# Positive_Ioniser.net
KiCad netlist of a schematic drawn in EAGLE
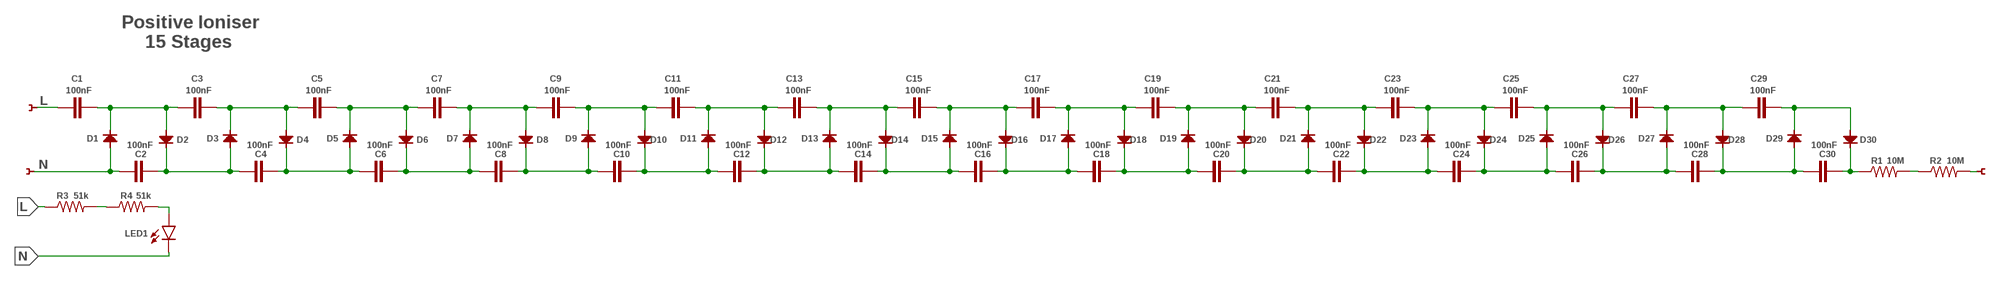
[diagram p0: schematic, sheet 1]

(export (version "E")
  (design (tool "Eeschema 10.0.6"))
  (components
    (comp (ref "C1")
      (value "100nF")
      (footprint "eagle-import:C1812")
      (fields (field (name "TOLERANCE") "±10%"))
      (libsource (lib "eagle-import") (part "CAPACITOR-1812"))
    )
    (comp (ref "C2")
      (value "100nF")
      (footprint "eagle-import:C1812")
      (fields
        (field (name "PART-NUM") "1812B104K631CT")
        (field (name "RATED") "630V")
        (field (name "TOLERANCE") "±10%")
      )
      (libsource (lib "eagle-import") (part "CAPACITOR-1812"))
    )
    (comp (ref "C3")
      (value "100nF")
      (footprint "eagle-import:C1812")
      (fields
        (field (name "PART-NUM") "1812B104K631CT")
        (field (name "RATED") "630V")
        (field (name "TOLERANCE") "±10%")
      )
      (libsource (lib "eagle-import") (part "CAPACITOR-1812"))
    )
    (comp (ref "C4")
      (value "100nF")
      (footprint "eagle-import:C1812")
      (fields
        (field (name "PART-NUM") "1812B104K631CT")
        (field (name "RATED") "630V")
        (field (name "TOLERANCE") "±10%")
      )
      (libsource (lib "eagle-import") (part "CAPACITOR-1812"))
    )
    (comp (ref "C5")
      (value "100nF")
      (footprint "eagle-import:C1812")
      (fields (field (name "TOLERANCE") "±10%"))
      (libsource (lib "eagle-import") (part "CAPACITOR-1812"))
    )
    (comp (ref "C6")
      (value "100nF")
      (footprint "eagle-import:C1812")
      (fields
        (field (name "PART-NUM") "1812B104K631CT")
        (field (name "RATED") "630V")
        (field (name "TOLERANCE") "±10%")
      )
      (libsource (lib "eagle-import") (part "CAPACITOR-1812"))
    )
    (comp (ref "C7")
      (value "100nF")
      (footprint "eagle-import:C1812")
      (fields
        (field (name "PART-NUM") "1812B104K631CT")
        (field (name "RATED") "630V")
        (field (name "TOLERANCE") "±10%")
      )
      (libsource (lib "eagle-import") (part "CAPACITOR-1812"))
    )
    (comp (ref "C8")
      (value "100nF")
      (footprint "eagle-import:C1812")
      (fields
        (field (name "PART-NUM") "1812B104K631CT")
        (field (name "RATED") "630V")
        (field (name "TOLERANCE") "±10%")
      )
      (libsource (lib "eagle-import") (part "CAPACITOR-1812"))
    )
    (comp (ref "C9")
      (value "100nF")
      (footprint "eagle-import:C1812")
      (fields (field (name "TOLERANCE") "±10%"))
      (libsource (lib "eagle-import") (part "CAPACITOR-1812"))
    )
    (comp (ref "C10")
      (value "100nF")
      (footprint "eagle-import:C1812")
      (fields
        (field (name "PART-NUM") "1812B104K631CT")
        (field (name "RATED") "630V")
        (field (name "TOLERANCE") "±10%")
      )
      (libsource (lib "eagle-import") (part "CAPACITOR-1812"))
    )
    (comp (ref "C11")
      (value "100nF")
      (footprint "eagle-import:C1812")
      (fields
        (field (name "PART-NUM") "1812B104K631CT")
        (field (name "RATED") "630V")
        (field (name "TOLERANCE") "±10%")
      )
      (libsource (lib "eagle-import") (part "CAPACITOR-1812"))
    )
    (comp (ref "C12")
      (value "100nF")
      (footprint "eagle-import:C1812")
      (fields
        (field (name "PART-NUM") "1812B104K631CT")
        (field (name "RATED") "630V")
        (field (name "TOLERANCE") "±10%")
      )
      (libsource (lib "eagle-import") (part "CAPACITOR-1812"))
    )
    (comp (ref "C13")
      (value "100nF")
      (footprint "eagle-import:C1812")
      (fields (field (name "TOLERANCE") "±10%"))
      (libsource (lib "eagle-import") (part "CAPACITOR-1812"))
    )
    (comp (ref "C14")
      (value "100nF")
      (footprint "eagle-import:C1812")
      (fields
        (field (name "PART-NUM") "1812B104K631CT")
        (field (name "RATED") "630V")
        (field (name "TOLERANCE") "±10%")
      )
      (libsource (lib "eagle-import") (part "CAPACITOR-1812"))
    )
    (comp (ref "C15")
      (value "100nF")
      (footprint "eagle-import:C1812")
      (fields
        (field (name "PART-NUM") "1812B104K631CT")
        (field (name "RATED") "630V")
        (field (name "TOLERANCE") "±10%")
      )
      (libsource (lib "eagle-import") (part "CAPACITOR-1812"))
    )
    (comp (ref "C16")
      (value "100nF")
      (footprint "eagle-import:C1812")
      (fields
        (field (name "PART-NUM") "1812B104K631CT")
        (field (name "RATED") "630V")
        (field (name "TOLERANCE") "±10%")
      )
      (libsource (lib "eagle-import") (part "CAPACITOR-1812"))
    )
    (comp (ref "C17")
      (value "100nF")
      (footprint "eagle-import:C1812")
      (fields (field (name "TOLERANCE") "±10%"))
      (libsource (lib "eagle-import") (part "CAPACITOR-1812"))
    )
    (comp (ref "C18")
      (value "100nF")
      (footprint "eagle-import:C1812")
      (fields
        (field (name "PART-NUM") "1812B104K631CT")
        (field (name "RATED") "630V")
        (field (name "TOLERANCE") "±10%")
      )
      (libsource (lib "eagle-import") (part "CAPACITOR-1812"))
    )
    (comp (ref "C19")
      (value "100nF")
      (footprint "eagle-import:C1812")
      (fields
        (field (name "PART-NUM") "1812B104K631CT")
        (field (name "RATED") "630V")
        (field (name "TOLERANCE") "±10%")
      )
      (libsource (lib "eagle-import") (part "CAPACITOR-1812"))
    )
    (comp (ref "C20")
      (value "100nF")
      (footprint "eagle-import:C1812")
      (fields
        (field (name "PART-NUM") "1812B104K631CT")
        (field (name "RATED") "630V")
        (field (name "TOLERANCE") "±10%")
      )
      (libsource (lib "eagle-import") (part "CAPACITOR-1812"))
    )
    (comp (ref "C21")
      (value "100nF")
      (footprint "eagle-import:C1812")
      (fields (field (name "TOLERANCE") "±10%"))
      (libsource (lib "eagle-import") (part "CAPACITOR-1812"))
    )
    (comp (ref "C22")
      (value "100nF")
      (footprint "eagle-import:C1812")
      (fields
        (field (name "PART-NUM") "1812B104K631CT")
        (field (name "RATED") "630V")
        (field (name "TOLERANCE") "±10%")
      )
      (libsource (lib "eagle-import") (part "CAPACITOR-1812"))
    )
    (comp (ref "C23")
      (value "100nF")
      (footprint "eagle-import:C1812")
      (fields
        (field (name "PART-NUM") "1812B104K631CT")
        (field (name "RATED") "630V")
        (field (name "TOLERANCE") "±10%")
      )
      (libsource (lib "eagle-import") (part "CAPACITOR-1812"))
    )
    (comp (ref "C24")
      (value "100nF")
      (footprint "eagle-import:C1812")
      (fields
        (field (name "PART-NUM") "1812B104K631CT")
        (field (name "RATED") "630V")
        (field (name "TOLERANCE") "±10%")
      )
      (libsource (lib "eagle-import") (part "CAPACITOR-1812"))
    )
    (comp (ref "C25")
      (value "100nF")
      (footprint "eagle-import:C1812")
      (fields (field (name "TOLERANCE") "±10%"))
      (libsource (lib "eagle-import") (part "CAPACITOR-1812"))
    )
    (comp (ref "C26")
      (value "100nF")
      (footprint "eagle-import:C1812")
      (fields
        (field (name "PART-NUM") "1812B104K631CT")
        (field (name "RATED") "630V")
        (field (name "TOLERANCE") "±10%")
      )
      (libsource (lib "eagle-import") (part "CAPACITOR-1812"))
    )
    (comp (ref "C27")
      (value "100nF")
      (footprint "eagle-import:C1812")
      (fields
        (field (name "PART-NUM") "1812B104K631CT")
        (field (name "RATED") "630V")
        (field (name "TOLERANCE") "±10%")
      )
      (libsource (lib "eagle-import") (part "CAPACITOR-1812"))
    )
    (comp (ref "C28")
      (value "100nF")
      (footprint "eagle-import:C1812")
      (fields
        (field (name "PART-NUM") "1812B104K631CT")
        (field (name "RATED") "630V")
        (field (name "TOLERANCE") "±10%")
      )
      (libsource (lib "eagle-import") (part "CAPACITOR-1812"))
    )
    (comp (ref "C29")
      (value "100nF")
      (footprint "eagle-import:C1812")
      (fields
        (field (name "PART-NUM") "1812B104K631CT")
        (field (name "RATED") "630V")
        (field (name "TOLERANCE") "±10%")
      )
      (libsource (lib "eagle-import") (part "CAPACITOR-1812"))
    )
    (comp (ref "C30")
      (value "100nF")
      (footprint "eagle-import:C1812")
      (fields
        (field (name "PART-NUM") "1812B104K631CT")
        (field (name "RATED") "630V")
        (field (name "TOLERANCE") "±10%")
      )
      (libsource (lib "eagle-import") (part "CAPACITOR-1812"))
    )
    (comp (ref "D1")
      (value "DIODE-1N4007")
      (footprint "eagle-import:DO-214A")
      (fields
        (field (name "I-RATING") "1A")
        (field (name "PART-NUM") "1N4007G")
        (field (name "V-RATING") "1kV")
      )
      (libsource (lib "eagle-import") (part "DIODE-1N4007"))
    )
    (comp (ref "D2")
      (value "DIODE-1N4007")
      (footprint "eagle-import:DO-214A")
      (fields
        (field (name "I-RATING") "1A")
        (field (name "PART-NUM") "1N4007G")
        (field (name "V-RATING") "1kV")
      )
      (libsource (lib "eagle-import") (part "DIODE-1N4007"))
    )
    (comp (ref "D3")
      (value "DIODE-1N4007")
      (footprint "eagle-import:DO-214A")
      (fields
        (field (name "I-RATING") "1A")
        (field (name "PART-NUM") "1N4007G")
        (field (name "V-RATING") "1kV")
      )
      (libsource (lib "eagle-import") (part "DIODE-1N4007"))
    )
    (comp (ref "D4")
      (value "DIODE-1N4007")
      (footprint "eagle-import:DO-214A")
      (fields
        (field (name "I-RATING") "1A")
        (field (name "PART-NUM") "1N4007G")
        (field (name "V-RATING") "1kV")
      )
      (libsource (lib "eagle-import") (part "DIODE-1N4007"))
    )
    (comp (ref "D5")
      (value "DIODE-1N4007")
      (footprint "eagle-import:DO-214A")
      (fields
        (field (name "I-RATING") "1A")
        (field (name "PART-NUM") "1N4007G")
        (field (name "V-RATING") "1kV")
      )
      (libsource (lib "eagle-import") (part "DIODE-1N4007"))
    )
    (comp (ref "D6")
      (value "DIODE-1N4007")
      (footprint "eagle-import:DO-214A")
      (fields
        (field (name "I-RATING") "1A")
        (field (name "PART-NUM") "1N4007G")
        (field (name "V-RATING") "1kV")
      )
      (libsource (lib "eagle-import") (part "DIODE-1N4007"))
    )
    (comp (ref "D7")
      (value "DIODE-1N4007")
      (footprint "eagle-import:DO-214A")
      (fields
        (field (name "I-RATING") "1A")
        (field (name "PART-NUM") "1N4007G")
        (field (name "V-RATING") "1kV")
      )
      (libsource (lib "eagle-import") (part "DIODE-1N4007"))
    )
    (comp (ref "D8")
      (value "DIODE-1N4007")
      (footprint "eagle-import:DO-214A")
      (fields
        (field (name "I-RATING") "1A")
        (field (name "PART-NUM") "1N4007G")
        (field (name "V-RATING") "1kV")
      )
      (libsource (lib "eagle-import") (part "DIODE-1N4007"))
    )
    (comp (ref "D9")
      (value "DIODE-1N4007")
      (footprint "eagle-import:DO-214A")
      (fields
        (field (name "I-RATING") "1A")
        (field (name "PART-NUM") "1N4007G")
        (field (name "V-RATING") "1kV")
      )
      (libsource (lib "eagle-import") (part "DIODE-1N4007"))
    )
    (comp (ref "D10")
      (value "DIODE-1N4007")
      (footprint "eagle-import:DO-214A")
      (fields
        (field (name "I-RATING") "1A")
        (field (name "PART-NUM") "1N4007G")
        (field (name "V-RATING") "1kV")
      )
      (libsource (lib "eagle-import") (part "DIODE-1N4007"))
    )
    (comp (ref "D11")
      (value "DIODE-1N4007")
      (footprint "eagle-import:DO-214A")
      (fields
        (field (name "I-RATING") "1A")
        (field (name "PART-NUM") "1N4007G")
        (field (name "V-RATING") "1kV")
      )
      (libsource (lib "eagle-import") (part "DIODE-1N4007"))
    )
    (comp (ref "D12")
      (value "DIODE-1N4007")
      (footprint "eagle-import:DO-214A")
      (fields
        (field (name "I-RATING") "1A")
        (field (name "PART-NUM") "1N4007G")
        (field (name "V-RATING") "1kV")
      )
      (libsource (lib "eagle-import") (part "DIODE-1N4007"))
    )
    (comp (ref "D13")
      (value "DIODE-1N4007")
      (footprint "eagle-import:DO-214A")
      (fields
        (field (name "I-RATING") "1A")
        (field (name "PART-NUM") "1N4007G")
        (field (name "V-RATING") "1kV")
      )
      (libsource (lib "eagle-import") (part "DIODE-1N4007"))
    )
    (comp (ref "D14")
      (value "DIODE-1N4007")
      (footprint "eagle-import:DO-214A")
      (fields
        (field (name "I-RATING") "1A")
        (field (name "PART-NUM") "1N4007G")
        (field (name "V-RATING") "1kV")
      )
      (libsource (lib "eagle-import") (part "DIODE-1N4007"))
    )
    (comp (ref "D15")
      (value "DIODE-1N4007")
      (footprint "eagle-import:DO-214A")
      (fields
        (field (name "I-RATING") "1A")
        (field (name "PART-NUM") "1N4007G")
        (field (name "V-RATING") "1kV")
      )
      (libsource (lib "eagle-import") (part "DIODE-1N4007"))
    )
    (comp (ref "D16")
      (value "DIODE-1N4007")
      (footprint "eagle-import:DO-214A")
      (fields
        (field (name "I-RATING") "1A")
        (field (name "PART-NUM") "1N4007G")
        (field (name "V-RATING") "1kV")
      )
      (libsource (lib "eagle-import") (part "DIODE-1N4007"))
    )
    (comp (ref "D17")
      (value "DIODE-1N4007")
      (footprint "eagle-import:DO-214A")
      (fields
        (field (name "I-RATING") "1A")
        (field (name "PART-NUM") "1N4007G")
        (field (name "V-RATING") "1kV")
      )
      (libsource (lib "eagle-import") (part "DIODE-1N4007"))
    )
    (comp (ref "D18")
      (value "DIODE-1N4007")
      (footprint "eagle-import:DO-214A")
      (fields
        (field (name "I-RATING") "1A")
        (field (name "PART-NUM") "1N4007G")
        (field (name "V-RATING") "1kV")
      )
      (libsource (lib "eagle-import") (part "DIODE-1N4007"))
    )
    (comp (ref "D19")
      (value "DIODE-1N4007")
      (footprint "eagle-import:DO-214A")
      (fields
        (field (name "I-RATING") "1A")
        (field (name "PART-NUM") "1N4007G")
        (field (name "V-RATING") "1kV")
      )
      (libsource (lib "eagle-import") (part "DIODE-1N4007"))
    )
    (comp (ref "D20")
      (value "DIODE-1N4007")
      (footprint "eagle-import:DO-214A")
      (fields
        (field (name "I-RATING") "1A")
        (field (name "PART-NUM") "1N4007G")
        (field (name "V-RATING") "1kV")
      )
      (libsource (lib "eagle-import") (part "DIODE-1N4007"))
    )
    (comp (ref "D21")
      (value "DIODE-1N4007")
      (footprint "eagle-import:DO-214A")
      (fields
        (field (name "I-RATING") "1A")
        (field (name "PART-NUM") "1N4007G")
        (field (name "V-RATING") "1kV")
      )
      (libsource (lib "eagle-import") (part "DIODE-1N4007"))
    )
    (comp (ref "D22")
      (value "DIODE-1N4007")
      (footprint "eagle-import:DO-214A")
      (fields
        (field (name "I-RATING") "1A")
        (field (name "PART-NUM") "1N4007G")
        (field (name "V-RATING") "1kV")
      )
      (libsource (lib "eagle-import") (part "DIODE-1N4007"))
    )
    (comp (ref "D23")
      (value "DIODE-1N4007")
      (footprint "eagle-import:DO-214A")
      (fields
        (field (name "I-RATING") "1A")
        (field (name "PART-NUM") "1N4007G")
        (field (name "V-RATING") "1kV")
      )
      (libsource (lib "eagle-import") (part "DIODE-1N4007"))
    )
    (comp (ref "D24")
      (value "DIODE-1N4007")
      (footprint "eagle-import:DO-214A")
      (fields
        (field (name "I-RATING") "1A")
        (field (name "PART-NUM") "1N4007G")
        (field (name "V-RATING") "1kV")
      )
      (libsource (lib "eagle-import") (part "DIODE-1N4007"))
    )
    (comp (ref "D25")
      (value "DIODE-1N4007")
      (footprint "eagle-import:DO-214A")
      (fields
        (field (name "I-RATING") "1A")
        (field (name "PART-NUM") "1N4007G")
        (field (name "V-RATING") "1kV")
      )
      (libsource (lib "eagle-import") (part "DIODE-1N4007"))
    )
    (comp (ref "D26")
      (value "DIODE-1N4007")
      (footprint "eagle-import:DO-214A")
      (fields
        (field (name "I-RATING") "1A")
        (field (name "PART-NUM") "1N4007G")
        (field (name "V-RATING") "1kV")
      )
      (libsource (lib "eagle-import") (part "DIODE-1N4007"))
    )
    (comp (ref "D27")
      (value "DIODE-1N4007")
      (footprint "eagle-import:DO-214A")
      (fields
        (field (name "I-RATING") "1A")
        (field (name "PART-NUM") "1N4007G")
        (field (name "V-RATING") "1kV")
      )
      (libsource (lib "eagle-import") (part "DIODE-1N4007"))
    )
    (comp (ref "D28")
      (value "DIODE-1N4007")
      (footprint "eagle-import:DO-214A")
      (fields
        (field (name "I-RATING") "1A")
        (field (name "PART-NUM") "1N4007G")
        (field (name "V-RATING") "1kV")
      )
      (libsource (lib "eagle-import") (part "DIODE-1N4007"))
    )
    (comp (ref "D29")
      (value "DIODE-1N4007")
      (footprint "eagle-import:DO-214A")
      (fields
        (field (name "I-RATING") "1A")
        (field (name "PART-NUM") "1N4007G")
        (field (name "V-RATING") "1kV")
      )
      (libsource (lib "eagle-import") (part "DIODE-1N4007"))
    )
    (comp (ref "D30")
      (value "DIODE-1N4007")
      (footprint "eagle-import:DO-214A")
      (fields
        (field (name "I-RATING") "1A")
        (field (name "PART-NUM") "1N4007G")
        (field (name "V-RATING") "1kV")
      )
      (libsource (lib "eagle-import") (part "DIODE-1N4007"))
    )
    (comp (ref "LED1")
      (value "LED-0603-SMD")
      (footprint "eagle-import:LED-0603")
      (fields (field (name "PART-NUM") "D-060306R1/SS2/L"))
      (libsource (lib "eagle-import") (part "LED-0603-SMD"))
    )
    (comp (ref "R1")
      (value "10M")
      (footprint "eagle-import:R1206")
      (fields
        (field (name "PART-NUM") "1206W4F1005T5E")
        (field (name "RATED") "0.25W")
        (field (name "TOLERANCE") "±1%")
      )
      (libsource (lib "eagle-import") (part "RESISTOR-1206"))
    )
    (comp (ref "R2")
      (value "10M")
      (footprint "eagle-import:R1206")
      (fields
        (field (name "PART-NUM") "1206W4F1005T5E")
        (field (name "RATED") "0.25W")
        (field (name "TOLERANCE") "±1%")
      )
      (libsource (lib "eagle-import") (part "RESISTOR-1206"))
    )
    (comp (ref "R3")
      (value "51k")
      (footprint "eagle-import:R1210")
      (fields
        (field (name "PART-NUM") "CR1210J51K0P05Z")
        (field (name "RATED") "0.5W")
        (field (name "TOLERANCE") "±5%")
      )
      (libsource (lib "eagle-import") (part "RESISTOR-1210"))
    )
    (comp (ref "R4")
      (value "51k")
      (footprint "eagle-import:R1210")
      (fields
        (field (name "PART-NUM") "CR1210J51K0P05Z")
        (field (name "RATED") "0.5W")
        (field (name "TOLERANCE") "±5%")
      )
      (libsource (lib "eagle-import") (part "RESISTOR-1210"))
    )
    (comp (ref "TP1")
      (value "TEST-POINT5MM")
      (footprint "eagle-import:SMD-SQ-PADS-5MM")
      (libsource (lib "eagle-import") (part "TEST-POINT5MM"))
    )
    (comp (ref "TP2")
      (value "TEST-POINT5MM")
      (footprint "eagle-import:SMD-SQ-PADS-5MM")
      (libsource (lib "eagle-import") (part "TEST-POINT5MM"))
    )
    (comp (ref "TP3")
      (value "TEST-POINT30X10")
      (footprint "eagle-import:LONG-RECT-PAD-50MM")
      (libsource (lib "eagle-import") (part "TEST-POINT30X10"))
    )
  )
  (nets
    (net (code "1") (name "L") (class "Default")
      (node (ref "C1") (pin "1") (pinfunction "1_1") (pintype "passive"))
      (node (ref "R3") (pin "1") (pinfunction "1_1") (pintype "passive"))
      (node (ref "TP1") (pin "P$1") (pinfunction "1_P$1") (pintype "bidirectional"))
    )
    (net (code "2") (name "N") (class "Default")
      (node (ref "C2") (pin "1") (pinfunction "1_1") (pintype "passive"))
      (node (ref "D1") (pin "ANODE") (pinfunction "A_ANODE") (pintype "bidirectional"))
      (node (ref "LED1") (pin "C") (pinfunction "C_C") (pintype "passive"))
      (node (ref "TP2") (pin "P$1") (pinfunction "1_P$1") (pintype "bidirectional"))
    )
    (net (code "3") (name "Net-(D1-C)") (class "Default")
      (node (ref "C1") (pin "2") (pinfunction "2_2") (pintype "passive"))
      (node (ref "C3") (pin "1") (pinfunction "1_1") (pintype "passive"))
      (node (ref "D1") (pin "CATHODE") (pinfunction "C_CATHODE") (pintype "bidirectional"))
      (node (ref "D2") (pin "ANODE") (pinfunction "A_ANODE") (pintype "bidirectional"))
    )
    (net (code "4") (name "Net-(D2-C)") (class "Default")
      (node (ref "C2") (pin "2") (pinfunction "2_2") (pintype "passive"))
      (node (ref "C4") (pin "1") (pinfunction "1_1") (pintype "passive"))
      (node (ref "D2") (pin "CATHODE") (pinfunction "C_CATHODE") (pintype "bidirectional"))
      (node (ref "D3") (pin "ANODE") (pinfunction "A_ANODE") (pintype "bidirectional"))
    )
    (net (code "5") (name "Net-(D3-C)") (class "Default")
      (node (ref "C3") (pin "2") (pinfunction "2_2") (pintype "passive"))
      (node (ref "C5") (pin "1") (pinfunction "1_1") (pintype "passive"))
      (node (ref "D3") (pin "CATHODE") (pinfunction "C_CATHODE") (pintype "bidirectional"))
      (node (ref "D4") (pin "ANODE") (pinfunction "A_ANODE") (pintype "bidirectional"))
    )
    (net (code "6") (name "Net-(D4-C)") (class "Default")
      (node (ref "C4") (pin "2") (pinfunction "2_2") (pintype "passive"))
      (node (ref "C6") (pin "1") (pinfunction "1_1") (pintype "passive"))
      (node (ref "D4") (pin "CATHODE") (pinfunction "C_CATHODE") (pintype "bidirectional"))
      (node (ref "D5") (pin "ANODE") (pinfunction "A_ANODE") (pintype "bidirectional"))
    )
    (net (code "7") (name "Net-(D5-C)") (class "Default")
      (node (ref "C5") (pin "2") (pinfunction "2_2") (pintype "passive"))
      (node (ref "C7") (pin "1") (pinfunction "1_1") (pintype "passive"))
      (node (ref "D5") (pin "CATHODE") (pinfunction "C_CATHODE") (pintype "bidirectional"))
      (node (ref "D6") (pin "ANODE") (pinfunction "A_ANODE") (pintype "bidirectional"))
    )
    (net (code "8") (name "Net-(D6-C)") (class "Default")
      (node (ref "C6") (pin "2") (pinfunction "2_2") (pintype "passive"))
      (node (ref "C8") (pin "1") (pinfunction "1_1") (pintype "passive"))
      (node (ref "D6") (pin "CATHODE") (pinfunction "C_CATHODE") (pintype "bidirectional"))
      (node (ref "D7") (pin "ANODE") (pinfunction "A_ANODE") (pintype "bidirectional"))
    )
    (net (code "9") (name "Net-(D7-C)") (class "Default")
      (node (ref "C7") (pin "2") (pinfunction "2_2") (pintype "passive"))
      (node (ref "C9") (pin "1") (pinfunction "1_1") (pintype "passive"))
      (node (ref "D7") (pin "CATHODE") (pinfunction "C_CATHODE") (pintype "bidirectional"))
      (node (ref "D8") (pin "ANODE") (pinfunction "A_ANODE") (pintype "bidirectional"))
    )
    (net (code "10") (name "Net-(D8-C)") (class "Default")
      (node (ref "C10") (pin "1") (pinfunction "1_1") (pintype "passive"))
      (node (ref "C8") (pin "2") (pinfunction "2_2") (pintype "passive"))
      (node (ref "D8") (pin "CATHODE") (pinfunction "C_CATHODE") (pintype "bidirectional"))
      (node (ref "D9") (pin "ANODE") (pinfunction "A_ANODE") (pintype "bidirectional"))
    )
    (net (code "11") (name "Net-(D10-A)") (class "Default")
      (node (ref "C11") (pin "1") (pinfunction "1_1") (pintype "passive"))
      (node (ref "C9") (pin "2") (pinfunction "2_2") (pintype "passive"))
      (node (ref "D10") (pin "ANODE") (pinfunction "A_ANODE") (pintype "bidirectional"))
      (node (ref "D9") (pin "CATHODE") (pinfunction "C_CATHODE") (pintype "bidirectional"))
    )
    (net (code "12") (name "Net-(D10-C)") (class "Default")
      (node (ref "C10") (pin "2") (pinfunction "2_2") (pintype "passive"))
      (node (ref "C12") (pin "1") (pinfunction "1_1") (pintype "passive"))
      (node (ref "D10") (pin "CATHODE") (pinfunction "C_CATHODE") (pintype "bidirectional"))
      (node (ref "D11") (pin "ANODE") (pinfunction "A_ANODE") (pintype "bidirectional"))
    )
    (net (code "13") (name "Net-(D11-C)") (class "Default")
      (node (ref "C11") (pin "2") (pinfunction "2_2") (pintype "passive"))
      (node (ref "C13") (pin "1") (pinfunction "1_1") (pintype "passive"))
      (node (ref "D11") (pin "CATHODE") (pinfunction "C_CATHODE") (pintype "bidirectional"))
      (node (ref "D12") (pin "ANODE") (pinfunction "A_ANODE") (pintype "bidirectional"))
    )
    (net (code "14") (name "Net-(D12-C)") (class "Default")
      (node (ref "C12") (pin "2") (pinfunction "2_2") (pintype "passive"))
      (node (ref "C14") (pin "1") (pinfunction "1_1") (pintype "passive"))
      (node (ref "D12") (pin "CATHODE") (pinfunction "C_CATHODE") (pintype "bidirectional"))
      (node (ref "D13") (pin "ANODE") (pinfunction "A_ANODE") (pintype "bidirectional"))
    )
    (net (code "15") (name "Net-(D13-C)") (class "Default")
      (node (ref "C13") (pin "2") (pinfunction "2_2") (pintype "passive"))
      (node (ref "C15") (pin "1") (pinfunction "1_1") (pintype "passive"))
      (node (ref "D13") (pin "CATHODE") (pinfunction "C_CATHODE") (pintype "bidirectional"))
      (node (ref "D14") (pin "ANODE") (pinfunction "A_ANODE") (pintype "bidirectional"))
    )
    (net (code "16") (name "Net-(D14-C)") (class "Default")
      (node (ref "C14") (pin "2") (pinfunction "2_2") (pintype "passive"))
      (node (ref "C16") (pin "1") (pinfunction "1_1") (pintype "passive"))
      (node (ref "D14") (pin "CATHODE") (pinfunction "C_CATHODE") (pintype "bidirectional"))
      (node (ref "D15") (pin "ANODE") (pinfunction "A_ANODE") (pintype "bidirectional"))
    )
    (net (code "17") (name "Net-(D15-C)") (class "Default")
      (node (ref "C15") (pin "2") (pinfunction "2_2") (pintype "passive"))
      (node (ref "C17") (pin "1") (pinfunction "1_1") (pintype "passive"))
      (node (ref "D15") (pin "CATHODE") (pinfunction "C_CATHODE") (pintype "bidirectional"))
      (node (ref "D16") (pin "ANODE") (pinfunction "A_ANODE") (pintype "bidirectional"))
    )
    (net (code "18") (name "Net-(D16-C)") (class "Default")
      (node (ref "C16") (pin "2") (pinfunction "2_2") (pintype "passive"))
      (node (ref "C18") (pin "1") (pinfunction "1_1") (pintype "passive"))
      (node (ref "D16") (pin "CATHODE") (pinfunction "C_CATHODE") (pintype "bidirectional"))
      (node (ref "D17") (pin "ANODE") (pinfunction "A_ANODE") (pintype "bidirectional"))
    )
    (net (code "19") (name "Net-(D17-C)") (class "Default")
      (node (ref "C17") (pin "2") (pinfunction "2_2") (pintype "passive"))
      (node (ref "C19") (pin "1") (pinfunction "1_1") (pintype "passive"))
      (node (ref "D17") (pin "CATHODE") (pinfunction "C_CATHODE") (pintype "bidirectional"))
      (node (ref "D18") (pin "ANODE") (pinfunction "A_ANODE") (pintype "bidirectional"))
    )
    (net (code "20") (name "Net-(D18-C)") (class "Default")
      (node (ref "C18") (pin "2") (pinfunction "2_2") (pintype "passive"))
      (node (ref "C20") (pin "1") (pinfunction "1_1") (pintype "passive"))
      (node (ref "D18") (pin "CATHODE") (pinfunction "C_CATHODE") (pintype "bidirectional"))
      (node (ref "D19") (pin "ANODE") (pinfunction "A_ANODE") (pintype "bidirectional"))
    )
    (net (code "21") (name "Net-(D19-C)") (class "Default")
      (node (ref "C19") (pin "2") (pinfunction "2_2") (pintype "passive"))
      (node (ref "C21") (pin "1") (pinfunction "1_1") (pintype "passive"))
      (node (ref "D19") (pin "CATHODE") (pinfunction "C_CATHODE") (pintype "bidirectional"))
      (node (ref "D20") (pin "ANODE") (pinfunction "A_ANODE") (pintype "bidirectional"))
    )
    (net (code "22") (name "Net-(D20-C)") (class "Default")
      (node (ref "C20") (pin "2") (pinfunction "2_2") (pintype "passive"))
      (node (ref "C22") (pin "1") (pinfunction "1_1") (pintype "passive"))
      (node (ref "D20") (pin "CATHODE") (pinfunction "C_CATHODE") (pintype "bidirectional"))
      (node (ref "D21") (pin "ANODE") (pinfunction "A_ANODE") (pintype "bidirectional"))
    )
    (net (code "23") (name "Net-(D21-C)") (class "Default")
      (node (ref "C21") (pin "2") (pinfunction "2_2") (pintype "passive"))
      (node (ref "C23") (pin "1") (pinfunction "1_1") (pintype "passive"))
      (node (ref "D21") (pin "CATHODE") (pinfunction "C_CATHODE") (pintype "bidirectional"))
      (node (ref "D22") (pin "ANODE") (pinfunction "A_ANODE") (pintype "bidirectional"))
    )
    (net (code "24") (name "Net-(D22-C)") (class "Default")
      (node (ref "C22") (pin "2") (pinfunction "2_2") (pintype "passive"))
      (node (ref "C24") (pin "1") (pinfunction "1_1") (pintype "passive"))
      (node (ref "D22") (pin "CATHODE") (pinfunction "C_CATHODE") (pintype "bidirectional"))
      (node (ref "D23") (pin "ANODE") (pinfunction "A_ANODE") (pintype "bidirectional"))
    )
    (net (code "25") (name "Net-(D23-C)") (class "Default")
      (node (ref "C23") (pin "2") (pinfunction "2_2") (pintype "passive"))
      (node (ref "C25") (pin "1") (pinfunction "1_1") (pintype "passive"))
      (node (ref "D23") (pin "CATHODE") (pinfunction "C_CATHODE") (pintype "bidirectional"))
      (node (ref "D24") (pin "ANODE") (pinfunction "A_ANODE") (pintype "bidirectional"))
    )
    (net (code "26") (name "Net-(D24-C)") (class "Default")
      (node (ref "C24") (pin "2") (pinfunction "2_2") (pintype "passive"))
      (node (ref "C26") (pin "1") (pinfunction "1_1") (pintype "passive"))
      (node (ref "D24") (pin "CATHODE") (pinfunction "C_CATHODE") (pintype "bidirectional"))
      (node (ref "D25") (pin "ANODE") (pinfunction "A_ANODE") (pintype "bidirectional"))
    )
    (net (code "27") (name "Net-(D25-C)") (class "Default")
      (node (ref "C25") (pin "2") (pinfunction "2_2") (pintype "passive"))
      (node (ref "C27") (pin "1") (pinfunction "1_1") (pintype "passive"))
      (node (ref "D25") (pin "CATHODE") (pinfunction "C_CATHODE") (pintype "bidirectional"))
      (node (ref "D26") (pin "ANODE") (pinfunction "A_ANODE") (pintype "bidirectional"))
    )
    (net (code "28") (name "Net-(D26-C)") (class "Default")
      (node (ref "C26") (pin "2") (pinfunction "2_2") (pintype "passive"))
      (node (ref "C28") (pin "1") (pinfunction "1_1") (pintype "passive"))
      (node (ref "D26") (pin "CATHODE") (pinfunction "C_CATHODE") (pintype "bidirectional"))
      (node (ref "D27") (pin "ANODE") (pinfunction "A_ANODE") (pintype "bidirectional"))
    )
    (net (code "29") (name "Net-(D27-C)") (class "Default")
      (node (ref "C27") (pin "2") (pinfunction "2_2") (pintype "passive"))
      (node (ref "C29") (pin "1") (pinfunction "1_1") (pintype "passive"))
      (node (ref "D27") (pin "CATHODE") (pinfunction "C_CATHODE") (pintype "bidirectional"))
      (node (ref "D28") (pin "ANODE") (pinfunction "A_ANODE") (pintype "bidirectional"))
    )
    (net (code "30") (name "Net-(D28-C)") (class "Default")
      (node (ref "C28") (pin "2") (pinfunction "2_2") (pintype "passive"))
      (node (ref "C30") (pin "1") (pinfunction "1_1") (pintype "passive"))
      (node (ref "D28") (pin "CATHODE") (pinfunction "C_CATHODE") (pintype "bidirectional"))
      (node (ref "D29") (pin "ANODE") (pinfunction "A_ANODE") (pintype "bidirectional"))
    )
    (net (code "31") (name "Net-(D29-C)") (class "Default")
      (node (ref "C29") (pin "2") (pinfunction "2_2") (pintype "passive"))
      (node (ref "D29") (pin "CATHODE") (pinfunction "C_CATHODE") (pintype "bidirectional"))
      (node (ref "D30") (pin "ANODE") (pinfunction "A_ANODE") (pintype "bidirectional"))
    )
    (net (code "32") (name "Net-(D30-C)") (class "Default")
      (node (ref "C30") (pin "2") (pinfunction "2_2") (pintype "passive"))
      (node (ref "D30") (pin "CATHODE") (pinfunction "C_CATHODE") (pintype "bidirectional"))
      (node (ref "R1") (pin "1") (pinfunction "1_1") (pintype "passive"))
    )
    (net (code "33") (name "Net-(LED1-PadA)") (class "Default")
      (node (ref "LED1") (pin "A") (pinfunction "A_A") (pintype "passive"))
      (node (ref "R4") (pin "2") (pinfunction "2_2") (pintype "passive"))
    )
    (net (code "34") (name "Net-(R1-Pad2)") (class "Default")
      (node (ref "R1") (pin "2") (pinfunction "2_2") (pintype "passive"))
      (node (ref "R2") (pin "1") (pinfunction "1_1") (pintype "passive"))
    )
    (net (code "35") (name "Net-(R2-Pad2)") (class "Default")
      (node (ref "R2") (pin "2") (pinfunction "2_2") (pintype "passive"))
      (node (ref "TP3") (pin "1") (pinfunction "1_1") (pintype "bidirectional"))
    )
    (net (code "36") (name "Net-(R3-Pad2)") (class "Default")
      (node (ref "R3") (pin "2") (pinfunction "2_2") (pintype "passive"))
      (node (ref "R4") (pin "1") (pinfunction "1_1") (pintype "passive"))
    )
  )
)
